# Sheet1.net
KiCad netlist of a schematic drawn in Altium Designer
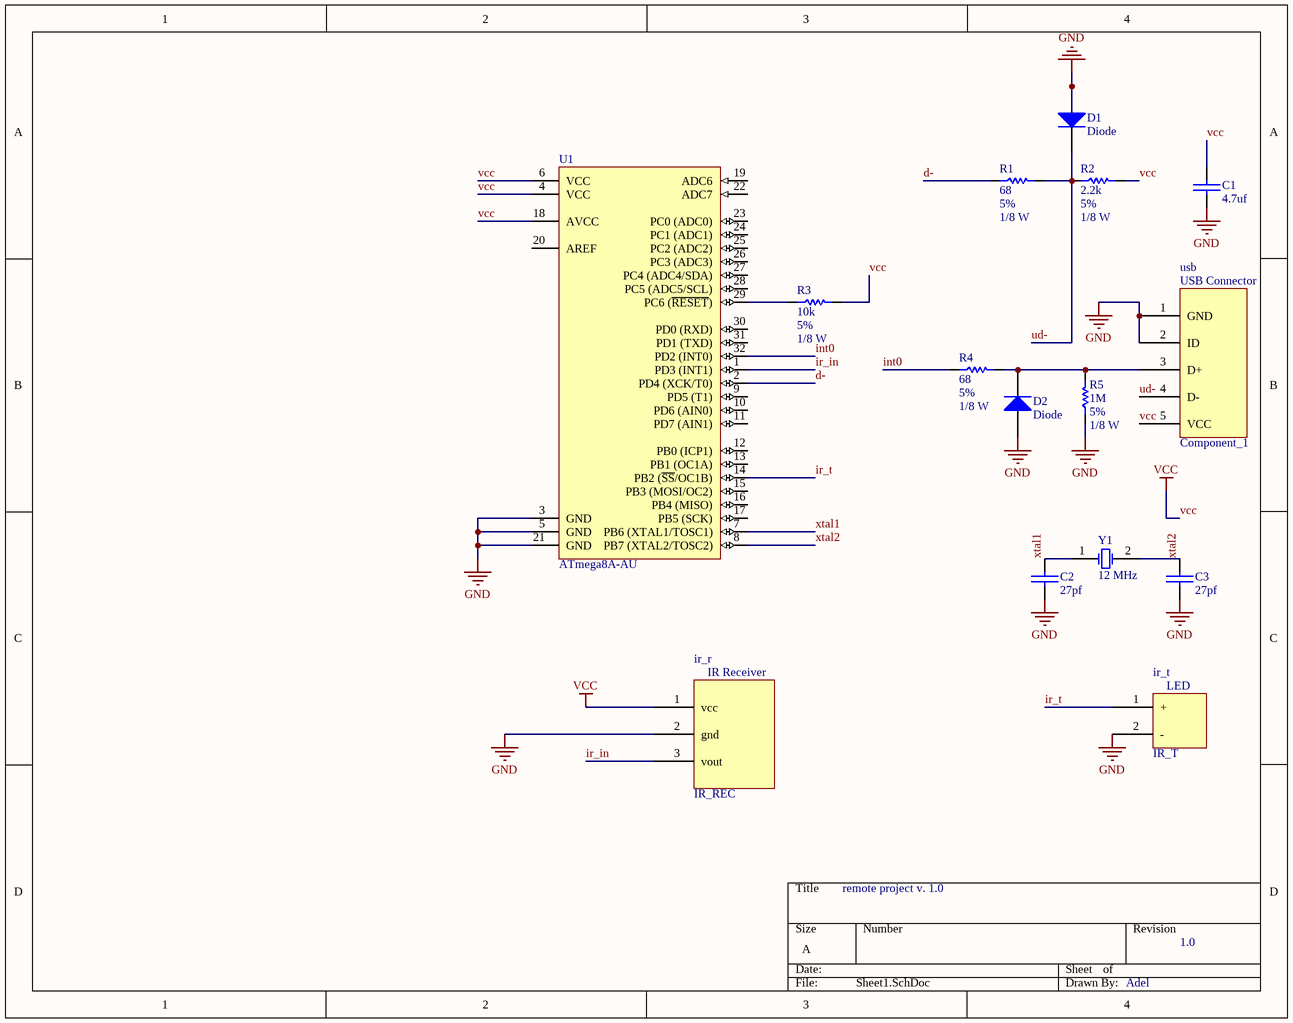
[diagram p0: Sheet1.SchDoc]

(export (version "E")
  (design (tool "Eeschema 10.0.6"))
  (components
    (comp (ref "C1")
      (value "4.7uf")
      (footprint "SMD_CAP_0805")
      (description "Bipolar Capacitor")
      (fields (field (name "VOLTAGE") "100V") (field (name "DESIGNER") "Saeid Jorablo"))
      (libsource (lib "Electrovolt Lib") (part "Cap-Bipolar"))
    )
    (comp (ref "C2")
      (value "27pf")
      (footprint "SMD_CAP_0805")
      (description "Bipolar Capacitor")
      (fields (field (name "VOLTAGE") "100V") (field (name "DESIGNER") "Saeid Jorablo"))
      (libsource (lib "Electrovolt Lib") (part "Cap-Bipolar"))
    )
    (comp (ref "C3")
      (value "27pf")
      (footprint "SMD_CAP_0805")
      (description "Bipolar Capacitor")
      (fields (field (name "VOLTAGE") "100V") (field (name "DESIGNER") "Saeid Jorablo"))
      (libsource (lib "Electrovolt Lib") (part "Cap-Bipolar"))
    )
    (comp (ref "D1")
      (value "Diode")
      (footprint "zener 2")
      (description "Default Diode")
      (fields (field (name "PUBLISHER") "Altium Limited"))
      (libsource (lib "Miscellaneous Devices") (part "Diode"))
    )
    (comp (ref "D2")
      (value "Diode")
      (footprint "zener 2")
      (description "Default Diode")
      (fields (field (name "PUBLISHER") "Altium Limited"))
      (libsource (lib "Miscellaneous Devices") (part "Diode"))
    )
    (comp (ref "ir_r")
      (value "IR_REC")
      (footprint "IR Receiver")
      (libsource (lib "Schlib3") (part "Component_1"))
    )
    (comp (ref "ir_t") (value "IR_T") (footprint "Diode") (libsource (lib "Schlib2") (part "Component_1")))
    (comp (ref "R1")
      (value "68")
      (footprint "RES 0805 (2012X06L)")
      (description "Resistor")
      (fields (field (name "TOLERANCE") "5%") (field (name "POWER") "1/8 W"))
      (libsource (lib "Electrovolt Lib") (part "Resistor"))
    )
    (comp (ref "R2")
      (value "2.2k")
      (footprint "RES 0805 (2012X06L)")
      (description "Resistor")
      (fields (field (name "TOLERANCE") "5%") (field (name "POWER") "1/8 W"))
      (libsource (lib "Electrovolt Lib") (part "Resistor"))
    )
    (comp (ref "R3")
      (value "10k")
      (footprint "RES 0805 (2012X06L)")
      (description "Resistor")
      (fields (field (name "TOLERANCE") "5%") (field (name "POWER") "1/8 W"))
      (libsource (lib "Electrovolt Lib") (part "Resistor"))
    )
    (comp (ref "R4")
      (value "68")
      (footprint "RES 0805 (2012X06L)")
      (description "Resistor")
      (fields (field (name "TOLERANCE") "5%") (field (name "POWER") "1/8 W"))
      (libsource (lib "Electrovolt Lib") (part "Resistor"))
    )
    (comp (ref "R5")
      (value "1M")
      (footprint "RES 0805 (2012X06L)")
      (description "Resistor")
      (fields (field (name "TOLERANCE") "5%") (field (name "POWER") "1/8 W"))
      (libsource (lib "Electrovolt Lib") (part "Resistor"))
    )
    (comp (ref "U1")
      (value "ATmega8A-AU")
      (footprint "32A_N")
      (fields (field (name "PUBLISHER") "Altium Limited"))
      (libsource (lib "Atmel Microcontroller 8-Bit megaAVR") (part "ATmega8A-AU"))
    )
    (comp (ref "usb")
      (value "Component_1")
      (footprint "USB Edge")
      (libsource (lib "Schlib1") (part "Component_1"))
    )
    (comp (ref "Y1")
      (value "12 MHz")
      (footprint "Crystal SMD")
      (description "XTAL Crystal")
      (libsource (lib "Electrovolt Lib") (part "XTAL"))
    )
  )
  (nets
    (net (code "1") (name "/d-") (class "Default")
      (node (ref "R1") (pin "1") (pinfunction "1_1") (pintype "passive"))
      (node (ref "U1") (pin "2") (pinfunction "PD4_(XCK/T0)_2") (pintype "bidirectional"))
    )
    (net (code "2") (name "/int0") (class "Default")
      (node (ref "R4") (pin "1") (pinfunction "1_1") (pintype "passive"))
      (node (ref "U1") (pin "32") (pinfunction "PD2_(INT0)_32") (pintype "bidirectional"))
    )
    (net (code "3") (name "/ir_in") (class "Default")
      (node (ref "U1") (pin "1") (pinfunction "PD3_(INT1)_1") (pintype "bidirectional"))
      (node (ref "ir_r") (pin "3") (pinfunction "vout_3") (pintype "passive"))
    )
    (net (code "4") (name "/ir_t") (class "Default")
      (node (ref "U1") (pin "14") (pinfunction "PB2_(~{SS}/OC1B)_14") (pintype "bidirectional"))
      (node (ref "ir_t") (pin "1") (pinfunction "+_1") (pintype "passive"))
    )
    (net (code "5") (name "/ud-") (class "Default")
      (node (ref "D1") (pin "2") (pinfunction "K_2") (pintype "passive"))
      (node (ref "R1") (pin "2") (pinfunction "2_2") (pintype "passive"))
      (node (ref "R2") (pin "1") (pinfunction "1_1") (pintype "passive"))
      (node (ref "usb") (pin "4") (pinfunction "D-_4") (pintype "passive"))
    )
    (net (code "6") (name "/xtal1") (class "Default")
      (node (ref "C2") (pin "1") (pinfunction "+_1") (pintype "passive"))
      (node (ref "U1") (pin "7") (pinfunction "PB6_(XTAL1/TOSC1)_7") (pintype "bidirectional"))
      (node (ref "Y1") (pin "1") (pinfunction "OSC1_1") (pintype "passive"))
    )
    (net (code "7") (name "/xtal2") (class "Default")
      (node (ref "C3") (pin "1") (pinfunction "+_1") (pintype "passive"))
      (node (ref "U1") (pin "8") (pinfunction "PB7_(XTAL2/TOSC2)_8") (pintype "bidirectional"))
      (node (ref "Y1") (pin "2") (pinfunction "OSC2_2") (pintype "passive"))
    )
    (net (code "8") (name "GND") (class "Default")
      (node (ref "C1") (pin "2") (pinfunction "-_2") (pintype "passive"))
      (node (ref "C2") (pin "2") (pinfunction "-_2") (pintype "passive"))
      (node (ref "C3") (pin "2") (pinfunction "-_2") (pintype "passive"))
      (node (ref "D1") (pin "1") (pinfunction "A_1") (pintype "passive"))
      (node (ref "D2") (pin "1") (pinfunction "A_1") (pintype "passive"))
      (node (ref "R5") (pin "1") (pinfunction "1_1") (pintype "passive"))
      (node (ref "U1") (pin "21") (pinfunction "GND_21") (pintype "power_in"))
      (node (ref "U1") (pin "3") (pinfunction "GND_3") (pintype "power_in"))
      (node (ref "U1") (pin "5") (pinfunction "GND_5") (pintype "power_in"))
      (node (ref "ir_r") (pin "2") (pinfunction "gnd_2") (pintype "passive"))
      (node (ref "ir_t") (pin "2") (pinfunction "-_2") (pintype "passive"))
      (node (ref "usb") (pin "1") (pinfunction "GND_1") (pintype "passive"))
      (node (ref "usb") (pin "2") (pinfunction "ID_2") (pintype "passive"))
    )
    (net (code "9") (name "Net-(D2-K)") (class "Default")
      (node (ref "D2") (pin "2") (pinfunction "K_2") (pintype "passive"))
      (node (ref "R4") (pin "2") (pinfunction "2_2") (pintype "passive"))
      (node (ref "R5") (pin "2") (pinfunction "2_2") (pintype "passive"))
      (node (ref "usb") (pin "3") (pinfunction "D+_3") (pintype "passive"))
    )
    (net (code "10") (name "Net-(U1-PC6_(~{RESET}))") (class "Default")
      (node (ref "R3") (pin "1") (pinfunction "1_1") (pintype "passive"))
      (node (ref "U1") (pin "29") (pinfunction "PC6_(~{RESET})_29") (pintype "bidirectional"))
    )
    (net (code "11") (name "VCC") (class "Default")
      (node (ref "C1") (pin "1") (pinfunction "+_1") (pintype "passive"))
      (node (ref "R2") (pin "2") (pinfunction "2_2") (pintype "passive"))
      (node (ref "R3") (pin "2") (pinfunction "2_2") (pintype "passive"))
      (node (ref "U1") (pin "18") (pinfunction "AVCC_18") (pintype "power_in"))
      (node (ref "U1") (pin "4") (pinfunction "VCC_4") (pintype "power_in"))
      (node (ref "U1") (pin "6") (pinfunction "VCC_6") (pintype "power_in"))
      (node (ref "ir_r") (pin "1") (pinfunction "vcc_1") (pintype "passive"))
      (node (ref "usb") (pin "5") (pinfunction "VCC_5") (pintype "passive"))
    )
    (net (code "12") (name "unconnected-(U1-ADC6-Pad19)") (class "Default")
      (node (ref "U1") (pin "19") (pinfunction "ADC6_19") (pintype "input"))
    )
    (net (code "13") (name "unconnected-(U1-ADC7-Pad22)") (class "Default")
      (node (ref "U1") (pin "22") (pinfunction "ADC7_22") (pintype "input"))
    )
    (net (code "14") (name "unconnected-(U1-AREF-Pad20)") (class "Default")
      (node (ref "U1") (pin "20") (pinfunction "AREF_20") (pintype "power_in"))
    )
    (net (code "15") (name "unconnected-(U1-PB0_(ICP1)-Pad12)") (class "Default")
      (node (ref "U1") (pin "12") (pinfunction "PB0_(ICP1)_12") (pintype "bidirectional"))
    )
    (net (code "16") (name "unconnected-(U1-PB1_(OC1A)-Pad13)") (class "Default")
      (node (ref "U1") (pin "13") (pinfunction "PB1_(OC1A)_13") (pintype "bidirectional"))
    )
    (net (code "17") (name "unconnected-(U1-PB3_(MOSI{slash}OC2)-Pad15)") (class "Default")
      (node (ref "U1") (pin "15") (pinfunction "PB3_(MOSI/OC2)_15") (pintype "bidirectional"))
    )
    (net (code "18") (name "unconnected-(U1-PB4_(MISO)-Pad16)") (class "Default")
      (node (ref "U1") (pin "16") (pinfunction "PB4_(MISO)_16") (pintype "bidirectional"))
    )
    (net (code "19") (name "unconnected-(U1-PB5_(SCK)-Pad17)") (class "Default")
      (node (ref "U1") (pin "17") (pinfunction "PB5_(SCK)_17") (pintype "bidirectional"))
    )
    (net (code "20") (name "unconnected-(U1-PC0_(ADC0)-Pad23)") (class "Default")
      (node (ref "U1") (pin "23") (pinfunction "PC0_(ADC0)_23") (pintype "bidirectional"))
    )
    (net (code "21") (name "unconnected-(U1-PC1_(ADC1)-Pad24)") (class "Default")
      (node (ref "U1") (pin "24") (pinfunction "PC1_(ADC1)_24") (pintype "bidirectional"))
    )
    (net (code "22") (name "unconnected-(U1-PC2_(ADC2)-Pad25)") (class "Default")
      (node (ref "U1") (pin "25") (pinfunction "PC2_(ADC2)_25") (pintype "bidirectional"))
    )
    (net (code "23") (name "unconnected-(U1-PC3_(ADC3)-Pad26)") (class "Default")
      (node (ref "U1") (pin "26") (pinfunction "PC3_(ADC3)_26") (pintype "bidirectional"))
    )
    (net (code "24") (name "unconnected-(U1-PC4_(ADC4{slash}SDA)-Pad27)") (class "Default")
      (node (ref "U1") (pin "27") (pinfunction "PC4_(ADC4/SDA)_27") (pintype "bidirectional"))
    )
    (net (code "25") (name "unconnected-(U1-PC5_(ADC5{slash}SCL)-Pad28)") (class "Default")
      (node (ref "U1") (pin "28") (pinfunction "PC5_(ADC5/SCL)_28") (pintype "bidirectional"))
    )
    (net (code "26") (name "unconnected-(U1-PD0_(RXD)-Pad30)") (class "Default")
      (node (ref "U1") (pin "30") (pinfunction "PD0_(RXD)_30") (pintype "bidirectional"))
    )
    (net (code "27") (name "unconnected-(U1-PD1_(TXD)-Pad31)") (class "Default")
      (node (ref "U1") (pin "31") (pinfunction "PD1_(TXD)_31") (pintype "bidirectional"))
    )
    (net (code "28") (name "unconnected-(U1-PD5_(T1)-Pad9)") (class "Default")
      (node (ref "U1") (pin "9") (pinfunction "PD5_(T1)_9") (pintype "bidirectional"))
    )
    (net (code "29") (name "unconnected-(U1-PD6_(AIN0)-Pad10)") (class "Default")
      (node (ref "U1") (pin "10") (pinfunction "PD6_(AIN0)_10") (pintype "bidirectional"))
    )
    (net (code "30") (name "unconnected-(U1-PD7_(AIN1)-Pad11)") (class "Default")
      (node (ref "U1") (pin "11") (pinfunction "PD7_(AIN1)_11") (pintype "bidirectional"))
    )
  )
)
